# Part19_UART_CP2104.net
KiCad netlist of a schematic drawn in Altium Designer
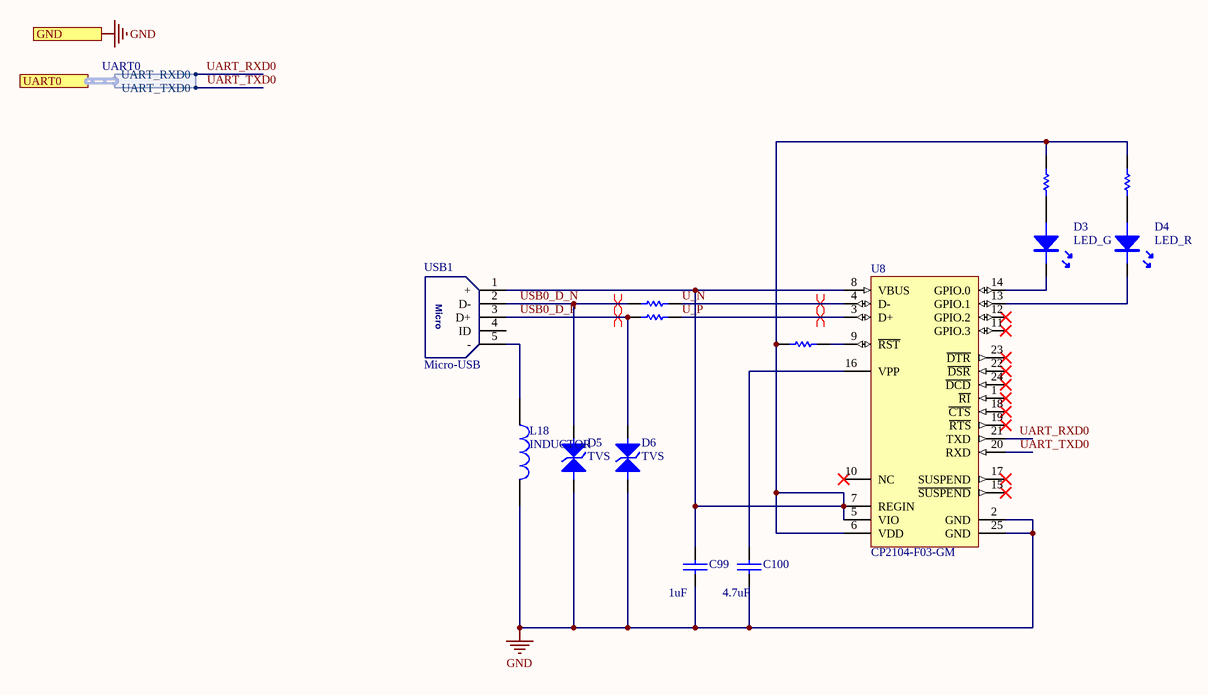
[diagram p0: Part19_UART_CP2104.SchDoc]

(export (version "E")
  (design (tool "Eeschema 10.0.6"))
  (components
    (comp (ref "C99")
      (value "1uF")
      (footprint "0603C")
      (description "无极性电容")
      (libsource (lib "电容") (part "CAP"))
    )
    (comp (ref "C100")
      (value "4.7uF")
      (footprint "0603C")
      (description "无极性电容")
      (libsource (lib "电容") (part "CAP"))
    )
    (comp (ref "D3") (value "LED_G") (footprint "LED-0603B") (libsource (lib "LED") (part "LED")))
    (comp (ref "D4") (value "LED_R") (footprint "LED-0603B") (libsource (lib "LED") (part "LED")))
    (comp (ref "D5")
      (value "TVS")
      (footprint "SOD-123")
      (description "双向瞬态抑制二极管")
      (libsource (lib "二极管") (part "TVS"))
    )
    (comp (ref "D6")
      (value "TVS")
      (footprint "SOD-123")
      (description "双向瞬态抑制二极管")
      (libsource (lib "二极管") (part "TVS"))
    )
    (comp (ref "L18") (value "INDUCTOR") (footprint "0603L") (libsource (lib "电感") (part "INDUCTOR")))
    (comp (ref "R77") (value "470R") (footprint "0402R") (libsource (lib "电阻") (part "RES")))
    (comp (ref "R78") (value "470R") (footprint "0402R") (libsource (lib "电阻") (part "RES")))
    (comp (ref "R79") (value "22R") (footprint "0402R") (libsource (lib "电阻") (part "RES")))
    (comp (ref "R80") (value "22R") (footprint "0402R") (libsource (lib "电阻") (part "RES")))
    (comp (ref "R81") (value "4.7k") (footprint "0402R") (libsource (lib "电阻") (part "RES")))
    (comp (ref "U8")
      (value "CP2104-F03-GM")
      (footprint "SLAB-QFN-24-2675x2675TP_M")
      (fields (field (name "MANUFACTURER") "Silicon Labs"))
      (libsource (lib "Altium Content Vault") (part "SLAB-CP2104-QFN-24-25"))
    )
    (comp (ref "USB1")
      (value "Micro-USB")
      (footprint "USB-micro_B")
      (libsource (lib "USB") (part "Micro-USB"))
    )
  )
  (nets
    (net (code "2") (name "/UART_RXD0") (class "Default")
      (node (ref "U8") (pin "21") (pinfunction "TXD_21") (pintype "output"))
    )
    (net (code "3") (name "/UART_TXD0") (class "Default")
      (node (ref "U8") (pin "20") (pinfunction "RXD_20") (pintype "input"))
    )
    (net (code "4") (name "/USB0_D_N") (class "Default")
      (node (ref "D5") (pin "A") (pinfunction "A_A") (pintype "passive"))
      (node (ref "R79") (pin "1") (pinfunction "1_1") (pintype "passive"))
      (node (ref "USB1") (pin "2") (pinfunction "D-_2") (pintype "passive"))
    )
    (net (code "5") (name "/USB0_D_P") (class "Default")
      (node (ref "D6") (pin "A") (pinfunction "A_A") (pintype "passive"))
      (node (ref "R80") (pin "1") (pinfunction "1_1") (pintype "passive"))
      (node (ref "USB1") (pin "3") (pinfunction "D+_3") (pintype "passive"))
    )
    (net (code "6") (name "/U_N") (class "Default")
      (node (ref "R79") (pin "2") (pinfunction "2_2") (pintype "passive"))
      (node (ref "U8") (pin "4") (pinfunction "D-_4") (pintype "bidirectional"))
    )
    (net (code "7") (name "/U_P") (class "Default")
      (node (ref "R80") (pin "2") (pinfunction "2_2") (pintype "passive"))
      (node (ref "U8") (pin "3") (pinfunction "D+_3") (pintype "bidirectional"))
    )
    (net (code "9") (name "GND") (class "Default")
      (node (ref "C100") (pin "1") (pinfunction "1_1") (pintype "passive"))
      (node (ref "C99") (pin "1") (pinfunction "1_1") (pintype "passive"))
      (node (ref "D5") (pin "K") (pinfunction "K_K") (pintype "passive"))
      (node (ref "D6") (pin "K") (pinfunction "K_K") (pintype "passive"))
      (node (ref "L18") (pin "2") (pinfunction "2_2") (pintype "passive"))
      (node (ref "U8") (pin "2") (pinfunction "GND_2") (pintype "power_in"))
      (node (ref "U8") (pin "25") (pinfunction "GND_25") (pintype "power_in"))
    )
    (net (code "10") (name "Net-(D3-PadA)") (class "Default")
      (node (ref "D3") (pin "A") (pinfunction "A_A") (pintype "passive"))
      (node (ref "R77") (pin "1") (pinfunction "1_1") (pintype "passive"))
    )
    (net (code "11") (name "Net-(D4-PadA)") (class "Default")
      (node (ref "D4") (pin "A") (pinfunction "A_A") (pintype "passive"))
      (node (ref "R78") (pin "1") (pinfunction "1_1") (pintype "passive"))
    )
    (net (code "12") (name "Net-(U8-GPIO.0)") (class "Default")
      (node (ref "D3") (pin "K") (pinfunction "K_K") (pintype "passive"))
      (node (ref "U8") (pin "14") (pinfunction "GPIO.0_14") (pintype "bidirectional"))
    )
    (net (code "13") (name "Net-(U8-GPIO.1)") (class "Default")
      (node (ref "D4") (pin "K") (pinfunction "K_K") (pintype "passive"))
      (node (ref "U8") (pin "13") (pinfunction "GPIO.1_13") (pintype "bidirectional"))
    )
    (net (code "14") (name "Net-(U8-REGIN)") (class "Default")
      (node (ref "C99") (pin "2") (pinfunction "2_2") (pintype "passive"))
      (node (ref "R77") (pin "2") (pinfunction "2_2") (pintype "passive"))
      (node (ref "R78") (pin "2") (pinfunction "2_2") (pintype "passive"))
      (node (ref "R81") (pin "1") (pinfunction "1_1") (pintype "passive"))
      (node (ref "U8") (pin "5") (pinfunction "VIO_5") (pintype "power_in"))
      (node (ref "U8") (pin "6") (pinfunction "VDD_6") (pintype "power_in"))
      (node (ref "U8") (pin "7") (pinfunction "REGIN_7") (pintype "power_in"))
      (node (ref "U8") (pin "8") (pinfunction "VBUS_8") (pintype "input"))
      (node (ref "USB1") (pin "1") (pinfunction "+_1") (pintype "passive"))
    )
    (net (code "15") (name "Net-(U8-VPP)") (class "Default")
      (node (ref "C100") (pin "2") (pinfunction "2_2") (pintype "passive"))
      (node (ref "U8") (pin "16") (pinfunction "VPP_16") (pintype "passive"))
    )
    (net (code "16") (name "Net-(U8-~{RST})") (class "Default")
      (node (ref "R81") (pin "2") (pinfunction "2_2") (pintype "passive"))
      (node (ref "U8") (pin "9") (pinfunction "~{RST}_9") (pintype "bidirectional"))
    )
    (net (code "17") (name "Net-(USB1--)") (class "Default")
      (node (ref "L18") (pin "1") (pinfunction "1_1") (pintype "passive"))
      (node (ref "USB1") (pin "5") (pinfunction "-_5") (pintype "passive"))
    )
    (net (code "18") (name "unconnected-(U8-GPIO.2-Pad12)") (class "Default")
      (node (ref "U8") (pin "12") (pinfunction "GPIO.2_12") (pintype "bidirectional+no_connect"))
    )
    (net (code "19") (name "unconnected-(U8-GPIO.3-Pad11)") (class "Default")
      (node (ref "U8") (pin "11") (pinfunction "GPIO.3_11") (pintype "bidirectional+no_connect"))
    )
    (net (code "20") (name "unconnected-(U8-NC-Pad10)") (class "Default")
      (node (ref "U8") (pin "10") (pinfunction "NC_10") (pintype "passive+no_connect"))
    )
    (net (code "21") (name "unconnected-(U8-SUSPEND-Pad17)") (class "Default")
      (node (ref "U8") (pin "17") (pinfunction "SUSPEND_17") (pintype "output+no_connect"))
    )
    (net (code "22") (name "unconnected-(U8-~{CTS}-Pad18)") (class "Default")
      (node (ref "U8") (pin "18") (pinfunction "~{CTS}_18") (pintype "input+no_connect"))
    )
    (net (code "23") (name "unconnected-(U8-~{DCD}-Pad24)") (class "Default")
      (node (ref "U8") (pin "24") (pinfunction "~{DCD}_24") (pintype "input+no_connect"))
    )
    (net (code "24") (name "unconnected-(U8-~{DSR}-Pad22)") (class "Default")
      (node (ref "U8") (pin "22") (pinfunction "~{DSR}_22") (pintype "input+no_connect"))
    )
    (net (code "25") (name "unconnected-(U8-~{DTR}-Pad23)") (class "Default")
      (node (ref "U8") (pin "23") (pinfunction "~{DTR}_23") (pintype "output+no_connect"))
    )
    (net (code "26") (name "unconnected-(U8-~{RI}-Pad1)") (class "Default")
      (node (ref "U8") (pin "1") (pinfunction "~{RI}_1") (pintype "input+no_connect"))
    )
    (net (code "27") (name "unconnected-(U8-~{RTS}-Pad19)") (class "Default")
      (node (ref "U8") (pin "19") (pinfunction "~{RTS}_19") (pintype "output+no_connect"))
    )
    (net (code "28") (name "unconnected-(U8-~{SUSPEND}-Pad15)") (class "Default")
      (node (ref "U8") (pin "15") (pinfunction "~{SUSPEND}_15") (pintype "output+no_connect"))
    )
    (net (code "29") (name "unconnected-(USB1-ID-Pad4)") (class "Default")
      (node (ref "USB1") (pin "4") (pinfunction "ID_4") (pintype "passive"))
    )
  )
)
